# BBB_eagle.net
KiCad netlist of a schematic drawn in EAGLE
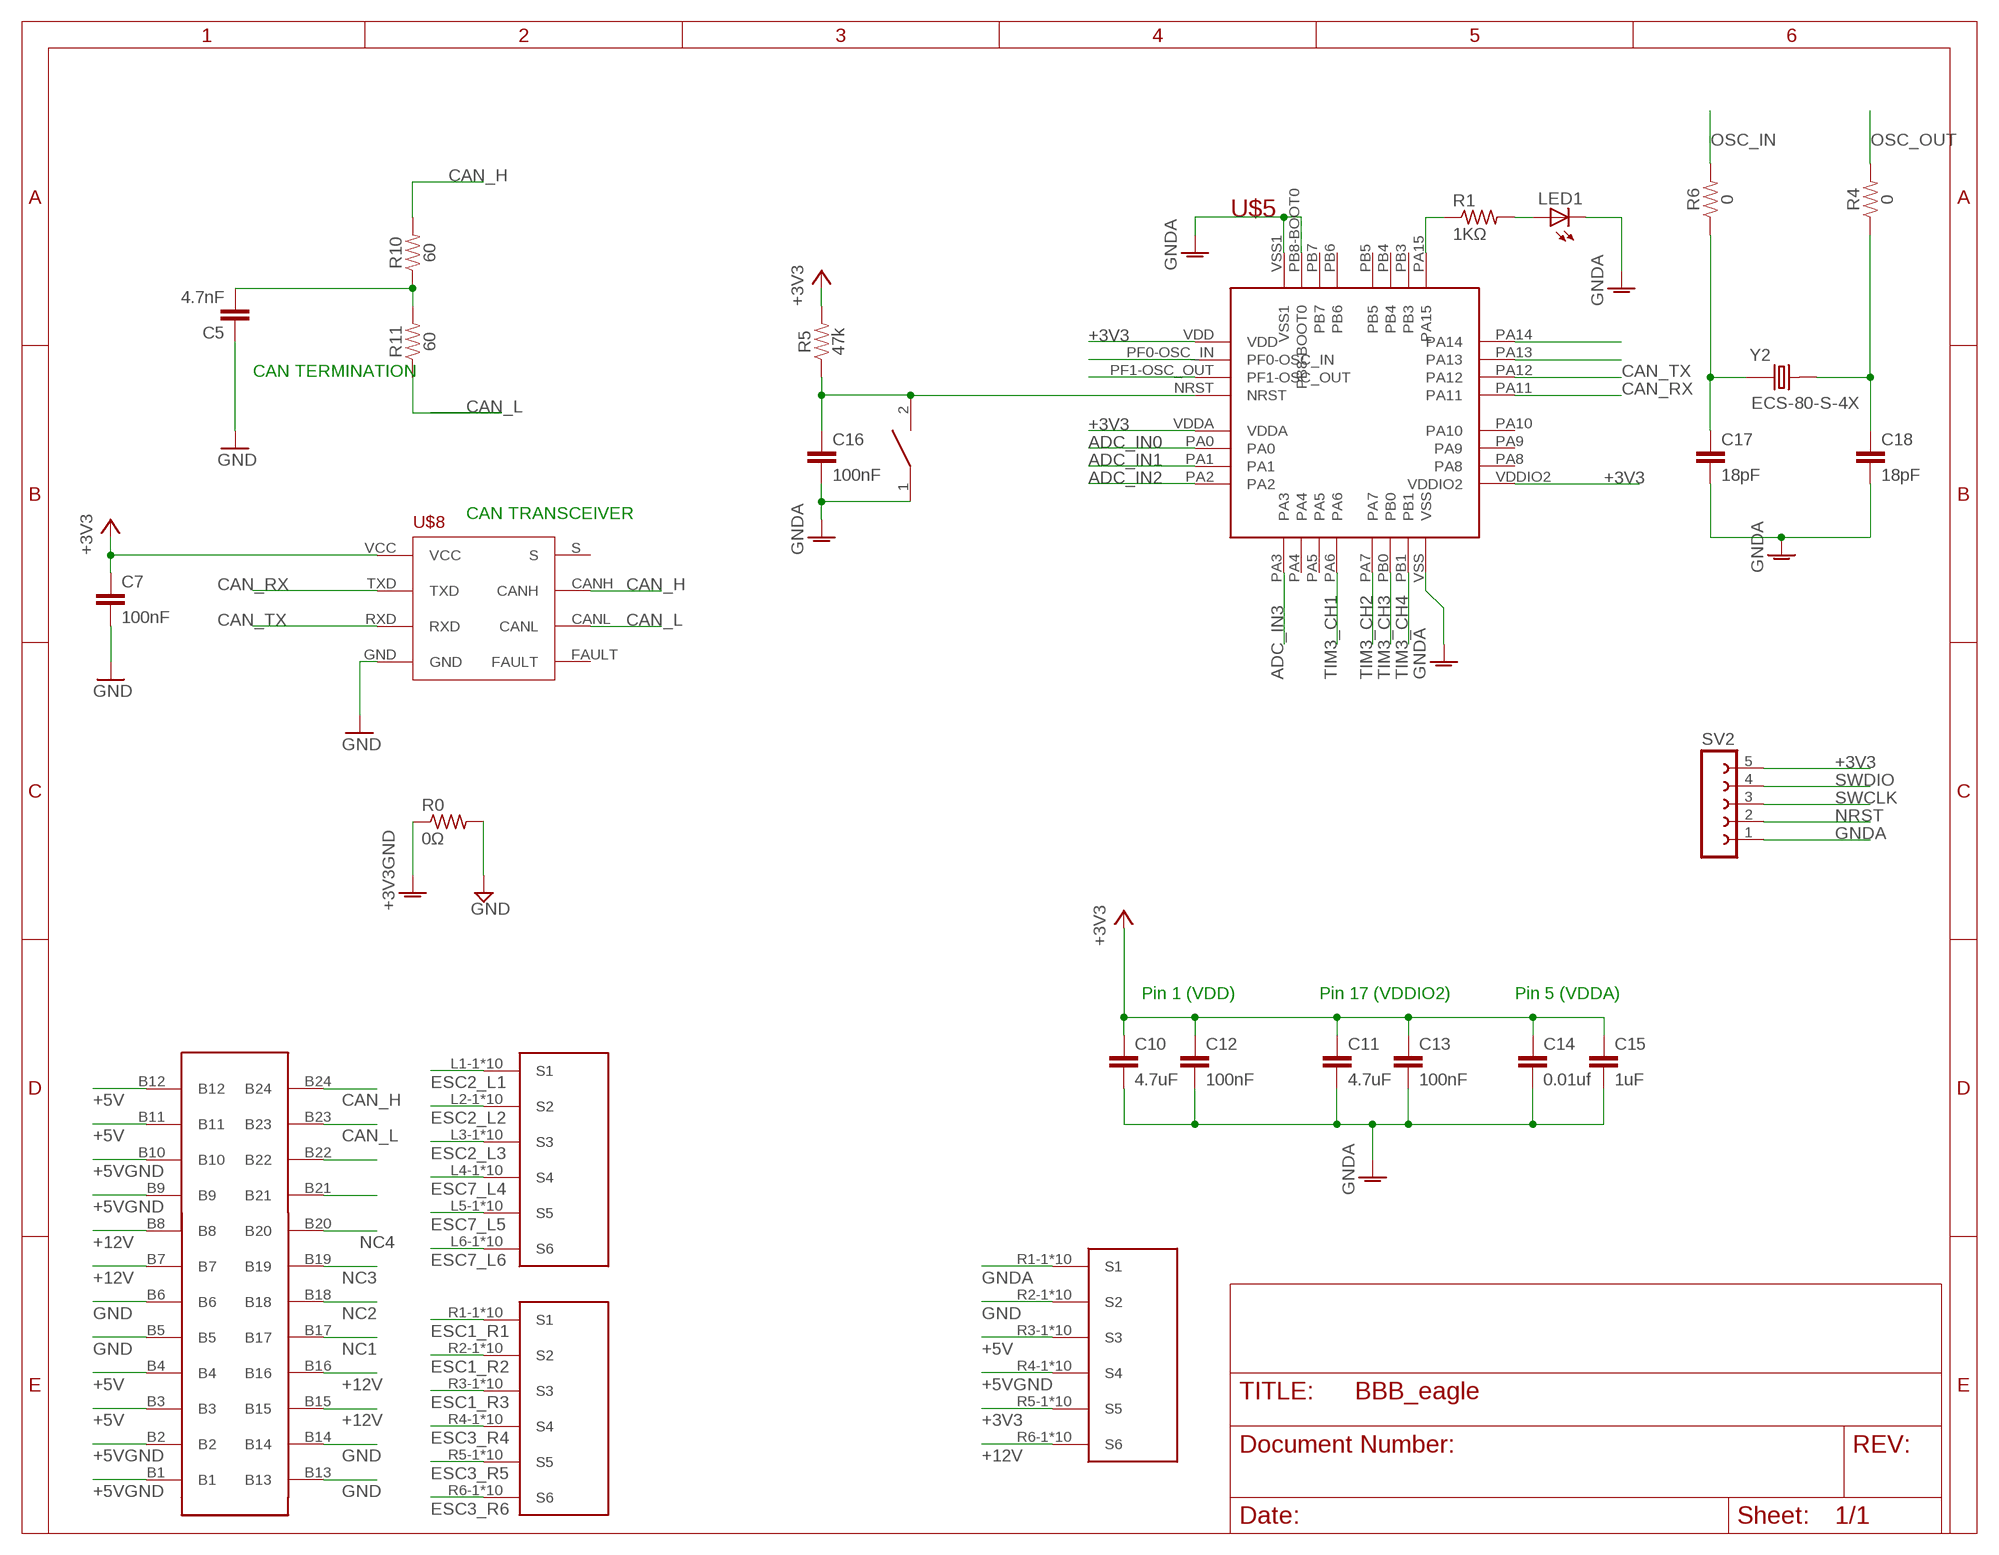
[diagram p0: schematic, sheet 1, part 1 of 2]
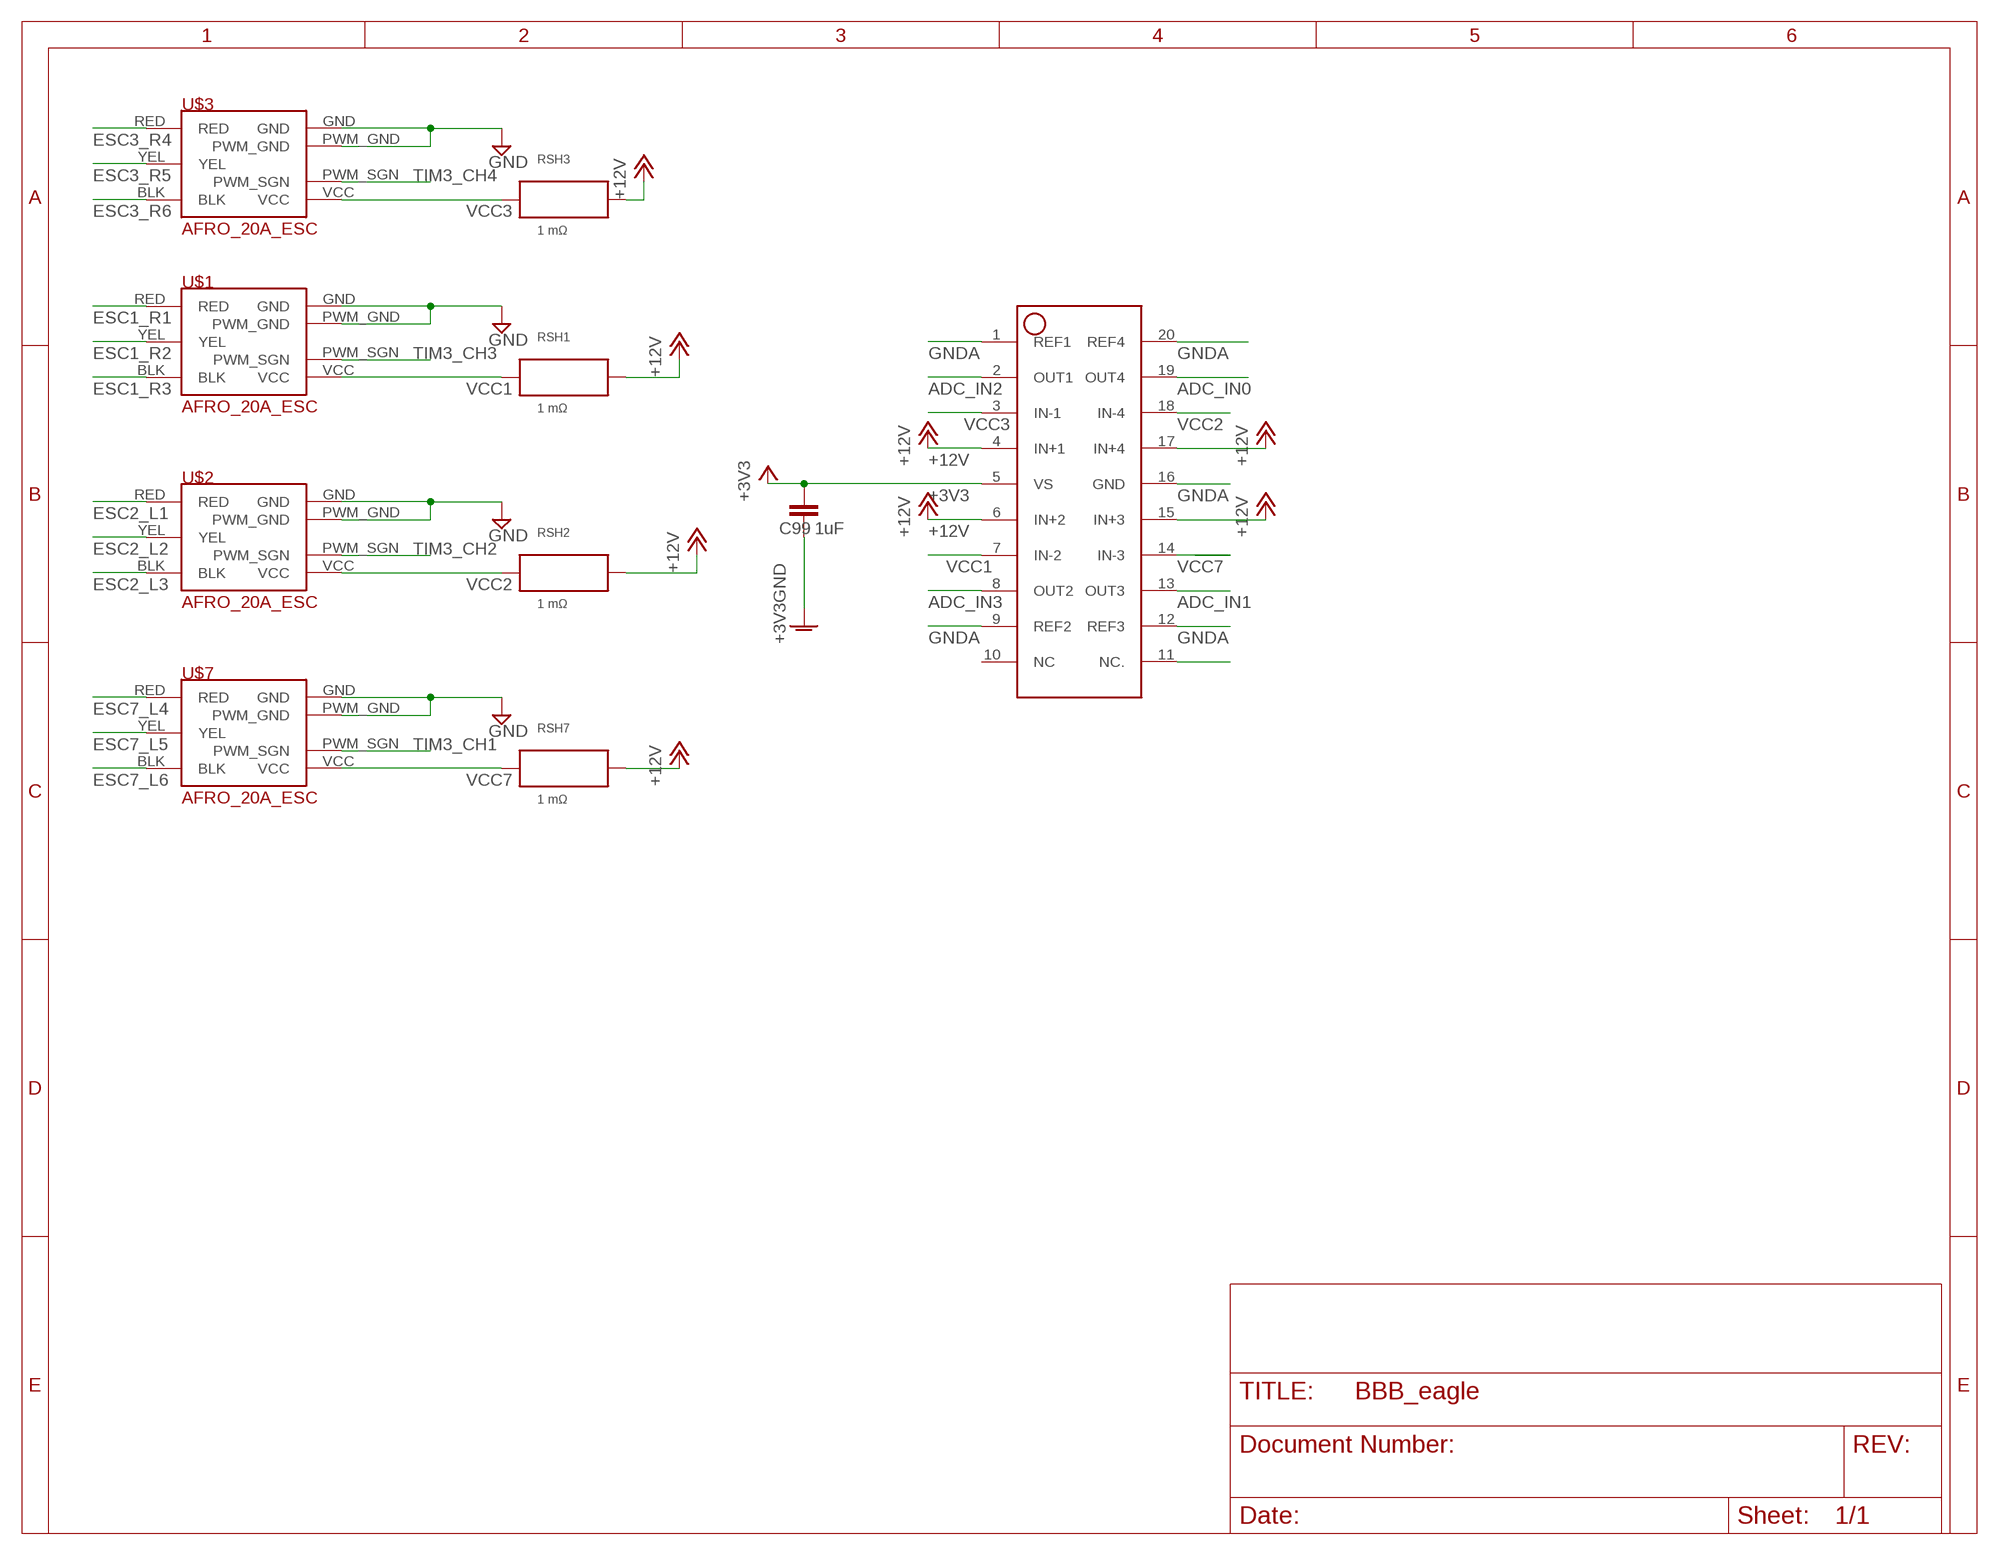
[diagram p1: schematic, sheet 1, part 2 of 2]

(export (version "E")
  (design (tool "Eeschema 10.0.6"))
  (components
    (comp (ref "C5")
      (value "4.7nF")
      (footprint "eagle-import:0603")
      (libsource (lib "eagle-import") (part "0.1UF-0603-25V-(+80/-20%)"))
    )
    (comp (ref "C7")
      (value "100nF")
      (footprint "eagle-import:0603")
      (libsource (lib "eagle-import") (part "4.7UF0603"))
    )
    (comp (ref "C10")
      (value "4.7uF")
      (footprint "eagle-import:0603")
      (libsource (lib "eagle-import") (part "4.7UF0603"))
    )
    (comp (ref "C11")
      (value "4.7uF")
      (footprint "eagle-import:0603")
      (libsource (lib "eagle-import") (part "4.7UF0603"))
    )
    (comp (ref "C12")
      (value "100nF")
      (footprint "eagle-import:0603")
      (libsource (lib "eagle-import") (part "4.7UF0603"))
    )
    (comp (ref "C13")
      (value "100nF")
      (footprint "eagle-import:0603")
      (libsource (lib "eagle-import") (part "4.7UF0603"))
    )
    (comp (ref "C14")
      (value "0.01uf")
      (footprint "eagle-import:0603")
      (libsource (lib "eagle-import") (part "4.7UF0603"))
    )
    (comp (ref "C15")
      (value "1uF")
      (footprint "eagle-import:0603")
      (libsource (lib "eagle-import") (part "4.7UF0603"))
    )
    (comp (ref "C16")
      (value "100nF")
      (footprint "eagle-import:0603")
      (libsource (lib "eagle-import") (part "4.7UF0603"))
    )
    (comp (ref "C17")
      (value "18pF")
      (footprint "eagle-import:0603")
      (libsource (lib "eagle-import") (part "4.7UF0603"))
    )
    (comp (ref "C18")
      (value "18pF")
      (footprint "eagle-import:0603")
      (libsource (lib "eagle-import") (part "4.7UF0603"))
    )
    (comp (ref "C99")
      (value "1uF")
      (footprint "eagle-import:0603")
      (libsource (lib "eagle-import") (part "4.7UF0603"))
    )
    (comp (ref "LED1")
      (value "LEDCHIP-LED0805")
      (footprint "eagle-import:CHIP-LED0805")
      (libsource (lib "eagle-import") (part "LEDCHIP-LED0805"))
    )
    (comp (ref "R0")
      (value "0Ω")
      (footprint "eagle-import:R0603")
      (libsource (lib "eagle-import") (part "R-US_R0603"))
    )
    (comp (ref "R1")
      (value "1KΩ")
      (footprint "eagle-import:R0603")
      (libsource (lib "eagle-import") (part "R-US_R0603"))
    )
    (comp (ref "R4")
      (value "0")
      (footprint "eagle-import:0603")
      (libsource (lib "eagle-import") (part "1KOHM-0603-1/10W-1%"))
    )
    (comp (ref "R5")
      (value "47k")
      (footprint "eagle-import:0603")
      (libsource (lib "eagle-import") (part "1KOHM-0603-1/10W-1%"))
    )
    (comp (ref "R6")
      (value "0")
      (footprint "eagle-import:0603")
      (libsource (lib "eagle-import") (part "1KOHM-0603-1/10W-1%"))
    )
    (comp (ref "R10")
      (value "60")
      (footprint "eagle-import:0603")
      (libsource (lib "eagle-import") (part "1KOHM-0603-1/10W-1%"))
    )
    (comp (ref "R11")
      (value "60")
      (footprint "eagle-import:0603")
      (libsource (lib "eagle-import") (part "1KOHM-0603-1/10W-1%"))
    )
    (comp (ref "RESET1")
      (value "SWITCH")
      (footprint "eagle-import:SW_2512")
      (libsource (lib "eagle-import") (part "SWITCH"))
    )
    (comp (ref "RSH1")
      (value "1 mΩ")
      (footprint "eagle-import:CSS2H-2512")
      (libsource (lib "eagle-import") (part "CSS2H-2512"))
    )
    (comp (ref "RSH2")
      (value "1 mΩ")
      (footprint "eagle-import:CSS2H-2512")
      (libsource (lib "eagle-import") (part "CSS2H-2512"))
    )
    (comp (ref "RSH3")
      (value "1 mΩ")
      (footprint "eagle-import:CSS2H-2512")
      (libsource (lib "eagle-import") (part "CSS2H-2512"))
    )
    (comp (ref "RSH7")
      (value "1 mΩ")
      (footprint "eagle-import:CSS2H-2512")
      (libsource (lib "eagle-import") (part "CSS2H-2512"))
    )
    (comp (ref "SV2")
      (value "FE05-1")
      (footprint "eagle-import:FE05-1")
      (libsource (lib "eagle-import") (part "FE05-1"))
    )
    (comp (ref "U$1")
      (value "AFRO_20A_ESC")
      (footprint "eagle-import:AFRO_20A_ESC")
      (libsource (lib "eagle-import") (part "AFRO_20A_ESC"))
    )
    (comp (ref "U$2")
      (value "AFRO_20A_ESC")
      (footprint "eagle-import:AFRO_20A_ESC")
      (libsource (lib "eagle-import") (part "AFRO_20A_ESC"))
    )
    (comp (ref "U$3")
      (value "AFRO_20A_ESC")
      (footprint "eagle-import:AFRO_20A_ESC")
      (libsource (lib "eagle-import") (part "AFRO_20A_ESC"))
    )
    (comp (ref "U$4")
      (value "ET60T_1")
      (footprint "eagle-import:ET60T_1")
      (libsource (lib "eagle-import") (part "ET60T_1"))
    )
    (comp (ref "U$5")
      (value "STM32F042K6T6")
      (footprint "eagle-import:STM32F042K6T6")
      (libsource (lib "eagle-import") (part "STM32F042K6T6"))
    )
    (comp (ref "U$6")
      (value "ET60T_2")
      (footprint "eagle-import:ET60T_2")
      (libsource (lib "eagle-import") (part "ET60T_2"))
    )
    (comp (ref "U$7")
      (value "AFRO_20A_ESC")
      (footprint "eagle-import:AFRO_20A_ESC")
      (libsource (lib "eagle-import") (part "AFRO_20A_ESC"))
    )
    (comp (ref "U$8")
      (value "TCAN337D")
      (footprint "eagle-import:TCAN337D")
      (libsource (lib "eagle-import") (part "TCAN337D"))
    )
    (comp (ref "U$14")
      (value "INA4181A4")
      (footprint "eagle-import:SOP65P640X120-20")
      (libsource (lib "eagle-import") (part "INA4181A4"))
    )
    (comp (ref "Y2")
      (value "ECS-80-S-4X")
      (footprint "eagle-import:XTAL_ECS-80-S-4X")
      (fields (field (name "DIGI-KEY_PART_NUMBER") "X1057-ND") (field (name "MF") "ECS International"))
      (libsource (lib "eagle-import") (part "ECS-80-S-4X"))
    )
  )
  (nets
    (net (code "1") (name "+3V3") (class "Default")
      (node (ref "C10") (pin "1") (pinfunction "1_1") (pintype "passive"))
      (node (ref "C11") (pin "1") (pinfunction "1_1") (pintype "passive"))
      (node (ref "C12") (pin "1") (pinfunction "1_1") (pintype "passive"))
      (node (ref "C13") (pin "1") (pinfunction "1_1") (pintype "passive"))
      (node (ref "C14") (pin "1") (pinfunction "1_1") (pintype "passive"))
      (node (ref "C15") (pin "1") (pinfunction "1_1") (pintype "passive"))
      (node (ref "C7") (pin "1") (pinfunction "1_1") (pintype "passive"))
      (node (ref "C99") (pin "1") (pinfunction "1_1") (pintype "passive"))
      (node (ref "R5") (pin "2") (pinfunction "2_2") (pintype "passive"))
      (node (ref "SV2") (pin "5") (pinfunction "5_5") (pintype "passive"))
      (node (ref "U$14") (pin "5") (pinfunction "VS_5") (pintype "bidirectional"))
      (node (ref "U$5") (pin "VDD") (pinfunction "VDD_VDD") (pintype "bidirectional"))
      (node (ref "U$5") (pin "VDDA") (pinfunction "VDDA_VDDA") (pintype "bidirectional"))
      (node (ref "U$5") (pin "VDDIO2") (pinfunction "VDDIO2_VDDIO2") (pintype "bidirectional"))
      (node (ref "U$6") (pin "R5-1") (pinfunction "S5_R5-1") (pintype "bidirectional"))
      (node (ref "U$6") (pin "R5-10") (pinfunction "S5_R5-10") (pintype "bidirectional"))
      (node (ref "U$6") (pin "R5-2") (pinfunction "S5_R5-2") (pintype "bidirectional"))
      (node (ref "U$6") (pin "R5-3") (pinfunction "S5_R5-3") (pintype "bidirectional"))
      (node (ref "U$6") (pin "R5-4") (pinfunction "S5_R5-4") (pintype "bidirectional"))
      (node (ref "U$6") (pin "R5-5") (pinfunction "S5_R5-5") (pintype "bidirectional"))
      (node (ref "U$6") (pin "R5-6") (pinfunction "S5_R5-6") (pintype "bidirectional"))
      (node (ref "U$6") (pin "R5-7") (pinfunction "S5_R5-7") (pintype "bidirectional"))
      (node (ref "U$6") (pin "R5-8") (pinfunction "S5_R5-8") (pintype "bidirectional"))
      (node (ref "U$6") (pin "R5-9") (pinfunction "S5_R5-9") (pintype "bidirectional"))
      (node (ref "U$8") (pin "VCC") (pinfunction "VCC_VCC") (pintype "bidirectional"))
    )
    (net (code "2") (name "+3V3GND") (class "Default")
      (node (ref "C10") (pin "2") (pinfunction "2_2") (pintype "passive"))
      (node (ref "C11") (pin "2") (pinfunction "2_2") (pintype "passive"))
      (node (ref "C12") (pin "2") (pinfunction "2_2") (pintype "passive"))
      (node (ref "C13") (pin "2") (pinfunction "2_2") (pintype "passive"))
      (node (ref "C14") (pin "2") (pinfunction "2_2") (pintype "passive"))
      (node (ref "C15") (pin "2") (pinfunction "2_2") (pintype "passive"))
      (node (ref "C16") (pin "2") (pinfunction "2_2") (pintype "passive"))
      (node (ref "C17") (pin "2") (pinfunction "2_2") (pintype "passive"))
      (node (ref "C18") (pin "2") (pinfunction "2_2") (pintype "passive"))
      (node (ref "C99") (pin "2") (pinfunction "2_2") (pintype "passive"))
      (node (ref "LED1") (pin "C") (pinfunction "C_C") (pintype "passive"))
      (node (ref "R0") (pin "1") (pinfunction "1_1") (pintype "passive"))
      (node (ref "RESET1") (pin "1") (pinfunction "P$1_1") (pintype "bidirectional"))
      (node (ref "SV2") (pin "1") (pinfunction "1_1") (pintype "passive"))
      (node (ref "U$14") (pin "1") (pinfunction "REF1_1") (pintype "bidirectional"))
      (node (ref "U$14") (pin "12") (pinfunction "REF3_12") (pintype "bidirectional"))
      (node (ref "U$14") (pin "16") (pinfunction "GND_16") (pintype "bidirectional"))
      (node (ref "U$14") (pin "20") (pinfunction "REF4_20") (pintype "bidirectional"))
      (node (ref "U$14") (pin "9") (pinfunction "REF2_9") (pintype "bidirectional"))
      (node (ref "U$5") (pin "PB8-BOOT0") (pinfunction "PB8-BOOT0_PB8-BOOT0") (pintype "bidirectional"))
      (node (ref "U$5") (pin "VSS") (pinfunction "VSS_VSS") (pintype "bidirectional"))
      (node (ref "U$5") (pin "VSS1") (pinfunction "VSS1_VSS1") (pintype "bidirectional"))
      (node (ref "U$6") (pin "R1-1") (pinfunction "S1_R1-1") (pintype "bidirectional"))
      (node (ref "U$6") (pin "R1-10") (pinfunction "S1_R1-10") (pintype "bidirectional"))
      (node (ref "U$6") (pin "R1-2") (pinfunction "S1_R1-2") (pintype "bidirectional"))
      (node (ref "U$6") (pin "R1-3") (pinfunction "S1_R1-3") (pintype "bidirectional"))
      (node (ref "U$6") (pin "R1-4") (pinfunction "S1_R1-4") (pintype "bidirectional"))
      (node (ref "U$6") (pin "R1-5") (pinfunction "S1_R1-5") (pintype "bidirectional"))
      (node (ref "U$6") (pin "R1-6") (pinfunction "S1_R1-6") (pintype "bidirectional"))
      (node (ref "U$6") (pin "R1-7") (pinfunction "S1_R1-7") (pintype "bidirectional"))
      (node (ref "U$6") (pin "R1-8") (pinfunction "S1_R1-8") (pintype "bidirectional"))
      (node (ref "U$6") (pin "R1-9") (pinfunction "S1_R1-9") (pintype "bidirectional"))
    )
    (net (code "3") (name "+12V") (class "Default")
      (node (ref "RSH1") (pin "2") (pinfunction "2_2") (pintype "bidirectional"))
      (node (ref "RSH2") (pin "2") (pinfunction "2_2") (pintype "bidirectional"))
      (node (ref "RSH3") (pin "2") (pinfunction "2_2") (pintype "bidirectional"))
      (node (ref "RSH7") (pin "2") (pinfunction "2_2") (pintype "bidirectional"))
      (node (ref "U$14") (pin "15") (pinfunction "IN+3_15") (pintype "bidirectional"))
      (node (ref "U$14") (pin "17") (pinfunction "IN+4_17") (pintype "bidirectional"))
      (node (ref "U$14") (pin "4") (pinfunction "IN+1_4") (pintype "bidirectional"))
      (node (ref "U$14") (pin "6") (pinfunction "IN+2_6") (pintype "bidirectional"))
      (node (ref "U$4") (pin "B15") (pinfunction "B15_B15") (pintype "bidirectional"))
      (node (ref "U$4") (pin "B16") (pinfunction "B16_B16") (pintype "bidirectional"))
      (node (ref "U$4") (pin "B7") (pinfunction "B7_B7") (pintype "bidirectional"))
      (node (ref "U$4") (pin "B8") (pinfunction "B8_B8") (pintype "bidirectional"))
      (node (ref "U$6") (pin "R6-1") (pinfunction "S6_R6-1") (pintype "bidirectional"))
      (node (ref "U$6") (pin "R6-10") (pinfunction "S6_R6-10") (pintype "bidirectional"))
      (node (ref "U$6") (pin "R6-2") (pinfunction "S6_R6-2") (pintype "bidirectional"))
      (node (ref "U$6") (pin "R6-3") (pinfunction "S6_R6-3") (pintype "bidirectional"))
      (node (ref "U$6") (pin "R6-4") (pinfunction "S6_R6-4") (pintype "bidirectional"))
      (node (ref "U$6") (pin "R6-5") (pinfunction "S6_R6-5") (pintype "bidirectional"))
      (node (ref "U$6") (pin "R6-6") (pinfunction "S6_R6-6") (pintype "bidirectional"))
      (node (ref "U$6") (pin "R6-7") (pinfunction "S6_R6-7") (pintype "bidirectional"))
      (node (ref "U$6") (pin "R6-8") (pinfunction "S6_R6-8") (pintype "bidirectional"))
      (node (ref "U$6") (pin "R6-9") (pinfunction "S6_R6-9") (pintype "bidirectional"))
    )
    (net (code "4") (name "/+5V") (class "Default")
      (node (ref "U$4") (pin "B11") (pinfunction "B11_B11") (pintype "bidirectional"))
      (node (ref "U$4") (pin "B12") (pinfunction "B12_B12") (pintype "bidirectional"))
      (node (ref "U$4") (pin "B3") (pinfunction "B3_B3") (pintype "bidirectional"))
      (node (ref "U$4") (pin "B4") (pinfunction "B4_B4") (pintype "bidirectional"))
      (node (ref "U$6") (pin "R3-1") (pinfunction "S3_R3-1") (pintype "bidirectional"))
      (node (ref "U$6") (pin "R3-10") (pinfunction "S3_R3-10") (pintype "bidirectional"))
      (node (ref "U$6") (pin "R3-2") (pinfunction "S3_R3-2") (pintype "bidirectional"))
      (node (ref "U$6") (pin "R3-3") (pinfunction "S3_R3-3") (pintype "bidirectional"))
      (node (ref "U$6") (pin "R3-4") (pinfunction "S3_R3-4") (pintype "bidirectional"))
      (node (ref "U$6") (pin "R3-5") (pinfunction "S3_R3-5") (pintype "bidirectional"))
      (node (ref "U$6") (pin "R3-6") (pinfunction "S3_R3-6") (pintype "bidirectional"))
      (node (ref "U$6") (pin "R3-7") (pinfunction "S3_R3-7") (pintype "bidirectional"))
      (node (ref "U$6") (pin "R3-8") (pinfunction "S3_R3-8") (pintype "bidirectional"))
      (node (ref "U$6") (pin "R3-9") (pinfunction "S3_R3-9") (pintype "bidirectional"))
    )
    (net (code "5") (name "/+5VGND") (class "Default")
      (node (ref "U$4") (pin "B1") (pinfunction "B1_B1") (pintype "bidirectional"))
      (node (ref "U$4") (pin "B10") (pinfunction "B10_B10") (pintype "bidirectional"))
      (node (ref "U$4") (pin "B2") (pinfunction "B2_B2") (pintype "bidirectional"))
      (node (ref "U$4") (pin "B9") (pinfunction "B9_B9") (pintype "bidirectional"))
      (node (ref "U$6") (pin "R4-1") (pinfunction "S4_R4-1") (pintype "bidirectional"))
      (node (ref "U$6") (pin "R4-10") (pinfunction "S4_R4-10") (pintype "bidirectional"))
      (node (ref "U$6") (pin "R4-2") (pinfunction "S4_R4-2") (pintype "bidirectional"))
      (node (ref "U$6") (pin "R4-3") (pinfunction "S4_R4-3") (pintype "bidirectional"))
      (node (ref "U$6") (pin "R4-4") (pinfunction "S4_R4-4") (pintype "bidirectional"))
      (node (ref "U$6") (pin "R4-5") (pinfunction "S4_R4-5") (pintype "bidirectional"))
      (node (ref "U$6") (pin "R4-6") (pinfunction "S4_R4-6") (pintype "bidirectional"))
      (node (ref "U$6") (pin "R4-7") (pinfunction "S4_R4-7") (pintype "bidirectional"))
      (node (ref "U$6") (pin "R4-8") (pinfunction "S4_R4-8") (pintype "bidirectional"))
      (node (ref "U$6") (pin "R4-9") (pinfunction "S4_R4-9") (pintype "bidirectional"))
    )
    (net (code "6") (name "/ADC_IN0") (class "Default")
      (node (ref "U$14") (pin "19") (pinfunction "OUT4_19") (pintype "bidirectional"))
      (node (ref "U$5") (pin "PA0") (pinfunction "PA0_PA0") (pintype "bidirectional"))
    )
    (net (code "7") (name "/ADC_IN1") (class "Default")
      (node (ref "U$14") (pin "13") (pinfunction "OUT3_13") (pintype "bidirectional"))
      (node (ref "U$5") (pin "PA1") (pinfunction "PA1_PA1") (pintype "bidirectional"))
    )
    (net (code "8") (name "/ADC_IN2") (class "Default")
      (node (ref "U$14") (pin "2") (pinfunction "OUT1_2") (pintype "bidirectional"))
      (node (ref "U$5") (pin "PA2") (pinfunction "PA2_PA2") (pintype "bidirectional"))
    )
    (net (code "9") (name "/ADC_IN3") (class "Default")
      (node (ref "U$14") (pin "8") (pinfunction "OUT2_8") (pintype "bidirectional"))
      (node (ref "U$5") (pin "PA3") (pinfunction "PA3_PA3") (pintype "bidirectional"))
    )
    (net (code "10") (name "/CAN_H") (class "Default")
      (node (ref "R10") (pin "2") (pinfunction "2_2") (pintype "passive"))
      (node (ref "U$4") (pin "B24") (pinfunction "B24_B24") (pintype "bidirectional"))
      (node (ref "U$8") (pin "CANH") (pinfunction "CANH_CANH") (pintype "bidirectional"))
    )
    (net (code "11") (name "/CAN_L") (class "Default")
      (node (ref "R11") (pin "1") (pinfunction "1_1") (pintype "passive"))
      (node (ref "U$4") (pin "B23") (pinfunction "B23_B23") (pintype "bidirectional"))
      (node (ref "U$8") (pin "CANL") (pinfunction "CANL_CANL") (pintype "bidirectional"))
    )
    (net (code "12") (name "/CAN_RX") (class "Default")
      (node (ref "U$5") (pin "PA11") (pinfunction "PA11_PA11") (pintype "bidirectional"))
      (node (ref "U$8") (pin "TXD") (pinfunction "TXD_TXD") (pintype "bidirectional"))
    )
    (net (code "13") (name "/CAN_TX") (class "Default")
      (node (ref "U$5") (pin "PA12") (pinfunction "PA12_PA12") (pintype "bidirectional"))
      (node (ref "U$8") (pin "RXD") (pinfunction "RXD_RXD") (pintype "bidirectional"))
    )
    (net (code "14") (name "/ESC1_R1") (class "Default")
      (node (ref "U$1") (pin "RED") (pinfunction "RED_RED") (pintype "bidirectional"))
      (node (ref "U$4") (pin "R1-1") (pinfunction "S1_R1-1") (pintype "bidirectional"))
      (node (ref "U$4") (pin "R1-10") (pinfunction "S1_R1-10") (pintype "bidirectional"))
      (node (ref "U$4") (pin "R1-2") (pinfunction "S1_R1-2") (pintype "bidirectional"))
      (node (ref "U$4") (pin "R1-3") (pinfunction "S1_R1-3") (pintype "bidirectional"))
      (node (ref "U$4") (pin "R1-4") (pinfunction "S1_R1-4") (pintype "bidirectional"))
      (node (ref "U$4") (pin "R1-5") (pinfunction "S1_R1-5") (pintype "bidirectional"))
      (node (ref "U$4") (pin "R1-6") (pinfunction "S1_R1-6") (pintype "bidirectional"))
      (node (ref "U$4") (pin "R1-7") (pinfunction "S1_R1-7") (pintype "bidirectional"))
      (node (ref "U$4") (pin "R1-8") (pinfunction "S1_R1-8") (pintype "bidirectional"))
      (node (ref "U$4") (pin "R1-9") (pinfunction "S1_R1-9") (pintype "bidirectional"))
    )
    (net (code "15") (name "/ESC1_R2") (class "Default")
      (node (ref "U$1") (pin "YEL") (pinfunction "YEL_YEL") (pintype "bidirectional"))
      (node (ref "U$4") (pin "R2-1") (pinfunction "S2_R2-1") (pintype "bidirectional"))
      (node (ref "U$4") (pin "R2-10") (pinfunction "S2_R2-10") (pintype "bidirectional"))
      (node (ref "U$4") (pin "R2-2") (pinfunction "S2_R2-2") (pintype "bidirectional"))
      (node (ref "U$4") (pin "R2-3") (pinfunction "S2_R2-3") (pintype "bidirectional"))
      (node (ref "U$4") (pin "R2-4") (pinfunction "S2_R2-4") (pintype "bidirectional"))
      (node (ref "U$4") (pin "R2-5") (pinfunction "S2_R2-5") (pintype "bidirectional"))
      (node (ref "U$4") (pin "R2-6") (pinfunction "S2_R2-6") (pintype "bidirectional"))
      (node (ref "U$4") (pin "R2-7") (pinfunction "S2_R2-7") (pintype "bidirectional"))
      (node (ref "U$4") (pin "R2-8") (pinfunction "S2_R2-8") (pintype "bidirectional"))
      (node (ref "U$4") (pin "R2-9") (pinfunction "S2_R2-9") (pintype "bidirectional"))
    )
    (net (code "16") (name "/ESC1_R3") (class "Default")
      (node (ref "U$1") (pin "BLK") (pinfunction "BLK_BLK") (pintype "bidirectional"))
      (node (ref "U$4") (pin "R3-1") (pinfunction "S3_R3-1") (pintype "bidirectional"))
      (node (ref "U$4") (pin "R3-10") (pinfunction "S3_R3-10") (pintype "bidirectional"))
      (node (ref "U$4") (pin "R3-2") (pinfunction "S3_R3-2") (pintype "bidirectional"))
      (node (ref "U$4") (pin "R3-3") (pinfunction "S3_R3-3") (pintype "bidirectional"))
      (node (ref "U$4") (pin "R3-4") (pinfunction "S3_R3-4") (pintype "bidirectional"))
      (node (ref "U$4") (pin "R3-5") (pinfunction "S3_R3-5") (pintype "bidirectional"))
      (node (ref "U$4") (pin "R3-6") (pinfunction "S3_R3-6") (pintype "bidirectional"))
      (node (ref "U$4") (pin "R3-7") (pinfunction "S3_R3-7") (pintype "bidirectional"))
      (node (ref "U$4") (pin "R3-8") (pinfunction "S3_R3-8") (pintype "bidirectional"))
      (node (ref "U$4") (pin "R3-9") (pinfunction "S3_R3-9") (pintype "bidirectional"))
    )
    (net (code "17") (name "/ESC2_L1") (class "Default")
      (node (ref "U$2") (pin "RED") (pinfunction "RED_RED") (pintype "bidirectional"))
      (node (ref "U$4") (pin "L1-1") (pinfunction "S1_L1-1") (pintype "bidirectional"))
      (node (ref "U$4") (pin "L1-10") (pinfunction "S1_L1-10") (pintype "bidirectional"))
      (node (ref "U$4") (pin "L1-2") (pinfunction "S1_L1-2") (pintype "bidirectional"))
      (node (ref "U$4") (pin "L1-3") (pinfunction "S1_L1-3") (pintype "bidirectional"))
      (node (ref "U$4") (pin "L1-4") (pinfunction "S1_L1-4") (pintype "bidirectional"))
      (node (ref "U$4") (pin "L1-5") (pinfunction "S1_L1-5") (pintype "bidirectional"))
      (node (ref "U$4") (pin "L1-6") (pinfunction "S1_L1-6") (pintype "bidirectional"))
      (node (ref "U$4") (pin "L1-7") (pinfunction "S1_L1-7") (pintype "bidirectional"))
      (node (ref "U$4") (pin "L1-8") (pinfunction "S1_L1-8") (pintype "bidirectional"))
      (node (ref "U$4") (pin "L1-9") (pinfunction "S1_L1-9") (pintype "bidirectional"))
    )
    (net (code "18") (name "/ESC2_L2") (class "Default")
      (node (ref "U$2") (pin "YEL") (pinfunction "YEL_YEL") (pintype "bidirectional"))
      (node (ref "U$4") (pin "L2-1") (pinfunction "S2_L2-1") (pintype "bidirectional"))
      (node (ref "U$4") (pin "L2-10") (pinfunction "S2_L2-10") (pintype "bidirectional"))
      (node (ref "U$4") (pin "L2-2") (pinfunction "S2_L2-2") (pintype "bidirectional"))
      (node (ref "U$4") (pin "L2-3") (pinfunction "S2_L2-3") (pintype "bidirectional"))
      (node (ref "U$4") (pin "L2-4") (pinfunction "S2_L2-4") (pintype "bidirectional"))
      (node (ref "U$4") (pin "L2-5") (pinfunction "S2_L2-5") (pintype "bidirectional"))
      (node (ref "U$4") (pin "L2-6") (pinfunction "S2_L2-6") (pintype "bidirectional"))
      (node (ref "U$4") (pin "L2-7") (pinfunction "S2_L2-7") (pintype "bidirectional"))
      (node (ref "U$4") (pin "L2-8") (pinfunction "S2_L2-8") (pintype "bidirectional"))
      (node (ref "U$4") (pin "L2-9") (pinfunction "S2_L2-9") (pintype "bidirectional"))
    )
    (net (code "19") (name "/ESC2_L3") (class "Default")
      (node (ref "U$2") (pin "BLK") (pinfunction "BLK_BLK") (pintype "bidirectional"))
      (node (ref "U$4") (pin "L3-1") (pinfunction "S3_L3-1") (pintype "bidirectional"))
      (node (ref "U$4") (pin "L3-10") (pinfunction "S3_L3-10") (pintype "bidirectional"))
      (node (ref "U$4") (pin "L3-2") (pinfunction "S3_L3-2") (pintype "bidirectional"))
      (node (ref "U$4") (pin "L3-3") (pinfunction "S3_L3-3") (pintype "bidirectional"))
      (node (ref "U$4") (pin "L3-4") (pinfunction "S3_L3-4") (pintype "bidirectional"))
      (node (ref "U$4") (pin "L3-5") (pinfunction "S3_L3-5") (pintype "bidirectional"))
      (node (ref "U$4") (pin "L3-6") (pinfunction "S3_L3-6") (pintype "bidirectional"))
      (node (ref "U$4") (pin "L3-7") (pinfunction "S3_L3-7") (pintype "bidirectional"))
      (node (ref "U$4") (pin "L3-8") (pinfunction "S3_L3-8") (pintype "bidirectional"))
      (node (ref "U$4") (pin "L3-9") (pinfunction "S3_L3-9") (pintype "bidirectional"))
    )
    (net (code "20") (name "/ESC3_R4") (class "Default")
      (node (ref "U$3") (pin "RED") (pinfunction "RED_RED") (pintype "bidirectional"))
      (node (ref "U$4") (pin "R4-1") (pinfunction "S4_R4-1") (pintype "bidirectional"))
      (node (ref "U$4") (pin "R4-10") (pinfunction "S4_R4-10") (pintype "bidirectional"))
      (node (ref "U$4") (pin "R4-2") (pinfunction "S4_R4-2") (pintype "bidirectional"))
      (node (ref "U$4") (pin "R4-3") (pinfunction "S4_R4-3") (pintype "bidirectional"))
      (node (ref "U$4") (pin "R4-4") (pinfunction "S4_R4-4") (pintype "bidirectional"))
      (node (ref "U$4") (pin "R4-5") (pinfunction "S4_R4-5") (pintype "bidirectional"))
      (node (ref "U$4") (pin "R4-6") (pinfunction "S4_R4-6") (pintype "bidirectional"))
      (node (ref "U$4") (pin "R4-7") (pinfunction "S4_R4-7") (pintype "bidirectional"))
      (node (ref "U$4") (pin "R4-8") (pinfunction "S4_R4-8") (pintype "bidirectional"))
      (node (ref "U$4") (pin "R4-9") (pinfunction "S4_R4-9") (pintype "bidirectional"))
    )
    (net (code "21") (name "/ESC3_R5") (class "Default")
      (node (ref "U$3") (pin "YEL") (pinfunction "YEL_YEL") (pintype "bidirectional"))
      (node (ref "U$4") (pin "R5-1") (pinfunction "S5_R5-1") (pintype "bidirectional"))
      (node (ref "U$4") (pin "R5-10") (pinfunction "S5_R5-10") (pintype "bidirectional"))
      (node (ref "U$4") (pin "R5-2") (pinfunction "S5_R5-2") (pintype "bidirectional"))
      (node (ref "U$4") (pin "R5-3") (pinfunction "S5_R5-3") (pintype "bidirectional"))
      (node (ref "U$4") (pin "R5-4") (pinfunction "S5_R5-4") (pintype "bidirectional"))
      (node (ref "U$4") (pin "R5-5") (pinfunction "S5_R5-5") (pintype "bidirectional"))
      (node (ref "U$4") (pin "R5-6") (pinfunction "S5_R5-6") (pintype "bidirectional"))
      (node (ref "U$4") (pin "R5-7") (pinfunction "S5_R5-7") (pintype "bidirectional"))
      (node (ref "U$4") (pin "R5-8") (pinfunction "S5_R5-8") (pintype "bidirectional"))
      (node (ref "U$4") (pin "R5-9") (pinfunction "S5_R5-9") (pintype "bidirectional"))
    )
    (net (code "22") (name "/ESC3_R6") (class "Default")
      (node (ref "U$3") (pin "BLK") (pinfunction "BLK_BLK") (pintype "bidirectional"))
      (node (ref "U$4") (pin "R6-1") (pinfunction "S6_R6-1") (pintype "bidirectional"))
      (node (ref "U$4") (pin "R6-10") (pinfunction "S6_R6-10") (pintype "bidirectional"))
      (node (ref "U$4") (pin "R6-2") (pinfunction "S6_R6-2") (pintype "bidirectional"))
      (node (ref "U$4") (pin "R6-3") (pinfunction "S6_R6-3") (pintype "bidirectional"))
      (node (ref "U$4") (pin "R6-4") (pinfunction "S6_R6-4") (pintype "bidirectional"))
      (node (ref "U$4") (pin "R6-5") (pinfunction "S6_R6-5") (pintype "bidirectional"))
      (node (ref "U$4") (pin "R6-6") (pinfunction "S6_R6-6") (pintype "bidirectional"))
      (node (ref "U$4") (pin "R6-7") (pinfunction "S6_R6-7") (pintype "bidirectional"))
      (node (ref "U$4") (pin "R6-8") (pinfunction "S6_R6-8") (pintype "bidirectional"))
      (node (ref "U$4") (pin "R6-9") (pinfunction "S6_R6-9") (pintype "bidirectional"))
    )
    (net (code "23") (name "/ESC7_L4") (class "Default")
      (node (ref "U$4") (pin "L4-1") (pinfunction "S4_L4-1") (pintype "bidirectional"))
      (node (ref "U$4") (pin "L4-10") (pinfunction "S4_L4-10") (pintype "bidirectional"))
      (node (ref "U$4") (pin "L4-2") (pinfunction "S4_L4-2") (pintype "bidirectional"))
      (node (ref "U$4") (pin "L4-3") (pinfunction "S4_L4-3") (pintype "bidirectional"))
      (node (ref "U$4") (pin "L4-4") (pinfunction "S4_L4-4") (pintype "bidirectional"))
      (node (ref "U$4") (pin "L4-5") (pinfunction "S4_L4-5") (pintype "bidirectional"))
      (node (ref "U$4") (pin "L4-6") (pinfunction "S4_L4-6") (pintype "bidirectional"))
      (node (ref "U$4") (pin "L4-7") (pinfunction "S4_L4-7") (pintype "bidirectional"))
      (node (ref "U$4") (pin "L4-8") (pinfunction "S4_L4-8") (pintype "bidirectional"))
      (node (ref "U$4") (pin "L4-9") (pinfunction "S4_L4-9") (pintype "bidirectional"))
      (node (ref "U$7") (pin "RED") (pinfunction "RED_RED") (pintype "bidirectional"))
    )
    (net (code "24") (name "/ESC7_L5") (class "Default")
      (node (ref "U$4") (pin "L5-1") (pinfunction "S5_L5-1") (pintype "bidirectional"))
      (node (ref "U$4") (pin "L5-10") (pinfunction "S5_L5-10") (pintype "bidirectional"))
      (node (ref "U$4") (pin "L5-2") (pinfunction "S5_L5-2") (pintype "bidirectional"))
      (node (ref "U$4") (pin "L5-3") (pinfunction "S5_L5-3") (pintype "bidirectional"))
      (node (ref "U$4") (pin "L5-4") (pinfunction "S5_L5-4") (pintype "bidirectional"))
      (node (ref "U$4") (pin "L5-5") (pinfunction "S5_L5-5") (pintype "bidirectional"))
      (node (ref "U$4") (pin "L5-6") (pinfunction "S5_L5-6") (pintype "bidirectional"))
      (node (ref "U$4") (pin "L5-7") (pinfunction "S5_L5-7") (pintype "bidirectional"))
      (node (ref "U$4") (pin "L5-8") (pinfunction "S5_L5-8") (pintype "bidirectional"))
      (node (ref "U$4") (pin "L5-9") (pinfunction "S5_L5-9") (pintype "bidirectional"))
      (node (ref "U$7") (pin "YEL") (pinfunction "YEL_YEL") (pintype "bidirectional"))
    )
    (net (code "25") (name "/ESC7_L6") (class "Default")
      (node (ref "U$4") (pin "L6-1") (pinfunction "S6_L6-1") (pintype "bidirectional"))
      (node (ref "U$4") (pin "L6-10") (pinfunction "S6_L6-10") (pintype "bidirectional"))
      (node (ref "U$4") (pin "L6-2") (pinfunction "S6_L6-2") (pintype "bidirectional"))
      (node (ref "U$4") (pin "L6-3") (pinfunction "S6_L6-3") (pintype "bidirectional"))
      (node (ref "U$4") (pin "L6-4") (pinfunction "S6_L6-4") (pintype "bidirectional"))
      (node (ref "U$4") (pin "L6-5") (pinfunction "S6_L6-5") (pintype "bidirectional"))
      (node (ref "U$4") (pin "L6-6") (pinfunction "S6_L6-6") (pintype "bidirectional"))
      (node (ref "U$4") (pin "L6-7") (pinfunction "S6_L6-7") (pintype "bidirectional"))
      (node (ref "U$4") (pin "L6-8") (pinfunction "S6_L6-8") (pintype "bidirectional"))
      (node (ref "U$4") (pin "L6-9") (pinfunction "S6_L6-9") (pintype "bidirectional"))
      (node (ref "U$7") (pin "BLK") (pinfunction "BLK_BLK") (pintype "bidirectional"))
    )
    (net (code "26") (name "/NC1") (class "Default")
      (node (ref "U$4") (pin "B17") (pinfunction "B17_B17") (pintype "bidirectional"))
    )
    (net (code "27") (name "/NC2") (class "Default")
      (node (ref "U$4") (pin "B18") (pinfunction "B18_B18") (pintype "bidirectional"))
    )
    (net (code "28") (name "/NC3") (class "Default")
      (node (ref "U$4") (pin "B19") (pinfunction "B19_B19") (pintype "bidirectional"))
    )
    (net (code "29") (name "/NC4") (class "Default")
      (node (ref "U$4") (pin "B20") (pinfunction "B20_B20") (pintype "bidirectional"))
    )
    (net (code "30") (name "/NRST") (class "Default")
      (node (ref "C16") (pin "1") (pinfunction "1_1") (pintype "passive"))
      (node (ref "R5") (pin "1") (pinfunction "1_1") (pintype "passive"))
      (node (ref "RESET1") (pin "2") (pinfunction "P$2_2") (pintype "bidirectional"))
      (node (ref "SV2") (pin "2") (pinfunction "2_2") (pintype "passive"))
      (node (ref "U$5") (pin "NRST") (pinfunction "NRST_NRST") (pintype "bidirectional"))
    )
    (net (code "31") (name "/OSC_IN") (class "Default")
      (node (ref "R6") (pin "2") (pinfunction "2_2") (pintype "passive"))
      (node (ref "U$5") (pin "PF0-OSC_IN") (pinfunction "PF0-OSC_IN_PF0-OSC_IN") (pintype "bidirectional"))
    )
    (net (code "32") (name "/OSC_OUT") (class "Default")
      (node (ref "R4") (pin "2") (pinfunction "2_2") (pintype "passive"))
      (node (ref "U$5") (pin "PF1-OSC_OUT") (pinfunction "PF1-OSC_OUT_PF1-OSC_OUT") (pintype "bidirectional"))
    )
    (net (code "33") (name "/SWCLK") (class "Default")
      (node (ref "SV2") (pin "3") (pinfunction "3_3") (pintype "passive"))
      (node (ref "U$5") (pin "PA14") (pinfunction "PA14_PA14") (pintype "bidirectional"))
    )
    (net (code "34") (name "/SWDIO") (class "Default")
      (node (ref "SV2") (pin "4") (pinfunction "4_4") (pintype "passive"))
      (node (ref "U$5") (pin "PA13") (pinfunction "PA13_PA13") (pintype "bidirectional"))
    )
    (net (code "35") (name "/TIM3_CH1") (class "Default")
      (node (ref "U$5") (pin "PA6") (pinfunction "PA6_PA6") (pintype "bidirectional"))
      (node (ref "U$7") (pin "PWM_SGN") (pinfunction "PWM_SGN_PWM_SGN") (pintype "bidirectional"))
    )
    (net (code "36") (name "/TIM3_CH2") (class "Default")
      (node (ref "U$2") (pin "PWM_SGN") (pinfunction "PWM_SGN_PWM_SGN") (pintype "bidirectional"))
      (node (ref "U$5") (pin "PA7") (pinfunction "PA7_PA7") (pintype "bidirectional"))
    )
    (net (code "37") (name "/TIM3_CH3") (class "Default")
      (node (ref "U$1") (pin "PWM_SGN") (pinfunction "PWM_SGN_PWM_SGN") (pintype "bidirectional"))
      (node (ref "U$5") (pin "PB0") (pinfunction "PB0_PB0") (pintype "bidirectional"))
    )
    (net (code "38") (name "/TIM3_CH4") (class "Default")
      (node (ref "U$3") (pin "PWM_SGN") (pinfunction "PWM_SGN_PWM_SGN") (pintype "bidirectional"))
      (node (ref "U$5") (pin "PB1") (pinfunction "PB1_PB1") (pintype "bidirectional"))
    )
    (net (code "39") (name "/VCC1") (class "Default")
      (node (ref "RSH1") (pin "1") (pinfunction "1_1") (pintype "bidirectional"))
      (node (ref "U$1") (pin "VCC") (pinfunction "VCC_VCC") (pintype "bidirectional"))
      (node (ref "U$14") (pin "7") (pinfunction "IN-2_7") (pintype "bidirectional"))
    )
    (net (code "40") (name "/VCC2") (class "Default")
      (node (ref "RSH2") (pin "1") (pinfunction "1_1") (pintype "bidirectional"))
      (node (ref "U$14") (pin "18") (pinfunction "IN-4_18") (pintype "bidirectional"))
      (node (ref "U$2") (pin "VCC") (pinfunction "VCC_VCC") (pintype "bidirectional"))
    )
    (net (code "41") (name "/VCC3") (class "Default")
      (node (ref "RSH3") (pin "1") (pinfunction "1_1") (pintype "bidirectional"))
      (node (ref "U$14") (pin "3") (pinfunction "IN-1_3") (pintype "bidirectional"))
      (node (ref "U$3") (pin "VCC") (pinfunction "VCC_VCC") (pintype "bidirectional"))
    )
    (net (code "42") (name "/VCC7") (class "Default")
      (node (ref "RSH7") (pin "1") (pinfunction "1_1") (pintype "bidirectional"))
      (node (ref "U$14") (pin "14") (pinfunction "IN-3_14") (pintype "bidirectional"))
      (node (ref "U$7") (pin "VCC") (pinfunction "VCC_VCC") (pintype "bidirectional"))
    )
    (net (code "43") (name "GND") (class "Default")
      (node (ref "C5") (pin "1") (pinfunction "1_1") (pintype "passive"))
      (node (ref "C7") (pin "2") (pinfunction "2_2") (pintype "passive"))
      (node (ref "R0") (pin "2") (pinfunction "2_2") (pintype "passive"))
      (node (ref "U$1") (pin "GND") (pinfunction "GND_GND") (pintype "bidirectional"))
      (node (ref "U$1") (pin "PWM_GND") (pinfunction "PWM_GND_PWM_GND") (pintype "bidirectional"))
      (node (ref "U$2") (pin "GND") (pinfunction "GND_GND") (pintype "bidirectional"))
      (node (ref "U$2") (pin "PWM_GND") (pinfunction "PWM_GND_PWM_GND") (pintype "bidirectional"))
      (node (ref "U$3") (pin "GND") (pinfunction "GND_GND") (pintype "bidirectional"))
      (node (ref "U$3") (pin "PWM_GND") (pinfunction "PWM_GND_PWM_GND") (pintype "bidirectional"))
      (node (ref "U$4") (pin "B13") (pinfunction "B13_B13") (pintype "bidirectional"))
      (node (ref "U$4") (pin "B14") (pinfunction "B14_B14") (pintype "bidirectional"))
      (node (ref "U$4") (pin "B21") (pinfunction "B21_B21") (pintype "bidirectional"))
      (node (ref "U$4") (pin "B22") (pinfunction "B22_B22") (pintype "bidirectional"))
      (node (ref "U$4") (pin "B5") (pinfunction "B5_B5") (pintype "bidirectional"))
      (node (ref "U$4") (pin "B6") (pinfunction "B6_B6") (pintype "bidirectional"))
      (node (ref "U$6") (pin "R2-1") (pinfunction "S2_R2-1") (pintype "bidirectional"))
      (node (ref "U$6") (pin "R2-10") (pinfunction "S2_R2-10") (pintype "bidirectional"))
      (node (ref "U$6") (pin "R2-2") (pinfunction "S2_R2-2") (pintype "bidirectional"))
      (node (ref "U$6") (pin "R2-3") (pinfunction "S2_R2-3") (pintype "bidirectional"))
      (node (ref "U$6") (pin "R2-4") (pinfunction "S2_R2-4") (pintype "bidirectional"))
      (node (ref "U$6") (pin "R2-5") (pinfunction "S2_R2-5") (pintype "bidirectional"))
      (node (ref "U$6") (pin "R2-6") (pinfunction "S2_R2-6") (pintype "bidirectional"))
      (node (ref "U$6") (pin "R2-7") (pinfunction "S2_R2-7") (pintype "bidirectional"))
      (node (ref "U$6") (pin "R2-8") (pinfunction "S2_R2-8") (pintype "bidirectional"))
      (node (ref "U$6") (pin "R2-9") (pinfunction "S2_R2-9") (pintype "bidirectional"))
      (node (ref "U$7") (pin "GND") (pinfunction "GND_GND") (pintype "bidirectional"))
      (node (ref "U$7") (pin "PWM_GND") (pinfunction "PWM_GND_PWM_GND") (pintype "bidirectional"))
      (node (ref "U$8") (pin "GND") (pinfunction "GND_GND") (pintype "bidirectional"))
    )
    (net (code "44") (name "Net-(C5-Pad2)") (class "Default")
      (node (ref "C5") (pin "2") (pinfunction "2_2") (pintype "passive"))
      (node (ref "R10") (pin "1") (pinfunction "1_1") (pintype "passive"))
      (node (ref "R11") (pin "2") (pinfunction "2_2") (pintype "passive"))
    )
    (net (code "45") (name "Net-(C17-Pad1)") (class "Default")
      (node (ref "C17") (pin "1") (pinfunction "1_1") (pintype "passive"))
      (node (ref "R6") (pin "1") (pinfunction "1_1") (pintype "passive"))
      (node (ref "Y2") (pin "1") (pinfunction "1_1") (pintype "passive"))
    )
    (net (code "46") (name "Net-(C18-Pad1)") (class "Default")
      (node (ref "C18") (pin "1") (pinfunction "1_1") (pintype "passive"))
      (node (ref "R4") (pin "1") (pinfunction "1_1") (pintype "passive"))
      (node (ref "Y2") (pin "2") (pinfunction "2_2") (pintype "passive"))
    )
    (net (code "47") (name "Net-(LED1-PadA)") (class "Default")
      (node (ref "LED1") (pin "A") (pinfunction "A_A") (pintype "passive"))
      (node (ref "R1") (pin "2") (pinfunction "2_2") (pintype "passive"))
    )
    (net (code "48") (name "Net-(R1-Pad1)") (class "Default")
      (node (ref "R1") (pin "1") (pinfunction "1_1") (pintype "passive"))
      (node (ref "U$5") (pin "PA15") (pinfunction "PA15_PA15") (pintype "bidirectional"))
    )
    (net (code "49") (name "unconnected-(U$5-PadPA4)") (class "Default")
      (node (ref "U$5") (pin "PA4") (pinfunction "PA4_PA4") (pintype "bidirectional"))
    )
    (net (code "50") (name "unconnected-(U$5-PadPA5)") (class "Default")
      (node (ref "U$5") (pin "PA5") (pinfunction "PA5_PA5") (pintype "bidirectional"))
    )
    (net (code "51") (name "unconnected-(U$5-PadPA8)") (class "Default")
      (node (ref "U$5") (pin "PA8") (pinfunction "PA8_PA8") (pintype "bidirectional"))
    )
    (net (code "52") (name "unconnected-(U$5-PadPA9)") (class "Default")
      (node (ref "U$5") (pin "PA9") (pinfunction "PA9_PA9") (pintype "bidirectional"))
    )
    (net (code "53") (name "unconnected-(U$5-PadPA10)") (class "Default")
      (node (ref "U$5") (pin "PA10") (pinfunction "PA10_PA10") (pintype "bidirectional"))
    )
    (net (code "54") (name "unconnected-(U$5-PadPB3)") (class "Default")
      (node (ref "U$5") (pin "PB3") (pinfunction "PB3_PB3") (pintype "bidirectional"))
    )
    (net (code "55") (name "unconnected-(U$5-PadPB4)") (class "Default")
      (node (ref "U$5") (pin "PB4") (pinfunction "PB4_PB4") (pintype "bidirectional"))
    )
    (net (code "56") (name "unconnected-(U$5-PadPB5)") (class "Default")
      (node (ref "U$5") (pin "PB5") (pinfunction "PB5_PB5") (pintype "bidirectional"))
    )
    (net (code "57") (name "unconnected-(U$5-PadPB6)") (class "Default")
      (node (ref "U$5") (pin "PB6") (pinfunction "PB6_PB6") (pintype "bidirectional"))
    )
    (net (code "58") (name "unconnected-(U$5-PadPB7)") (class "Default")
      (node (ref "U$5") (pin "PB7") (pinfunction "PB7_PB7") (pintype "bidirectional"))
    )
    (net (code "59") (name "unconnected-(U$8-PadFAULT)") (class "Default")
      (node (ref "U$8") (pin "FAULT") (pinfunction "FAULT_FAULT") (pintype "bidirectional"))
    )
    (net (code "60") (name "unconnected-(U$8-PadS)") (class "Default")
      (node (ref "U$8") (pin "S") (pinfunction "S_S") (pintype "bidirectional"))
    )
    (net (code "61") (name "unconnected-(U$14-NC-Pad10)") (class "Default")
      (node (ref "U$14") (pin "10") (pinfunction "NC_10") (pintype "bidirectional"))
    )
    (net (code "62") (name "unconnected-(U$14-NC.-Pad11)") (class "Default")
      (node (ref "U$14") (pin "11") (pinfunction "NC._11") (pintype "bidirectional"))
    )
  )
)
